# ExternalConnections.net
KiCad netlist of a schematic drawn in Altium Designer
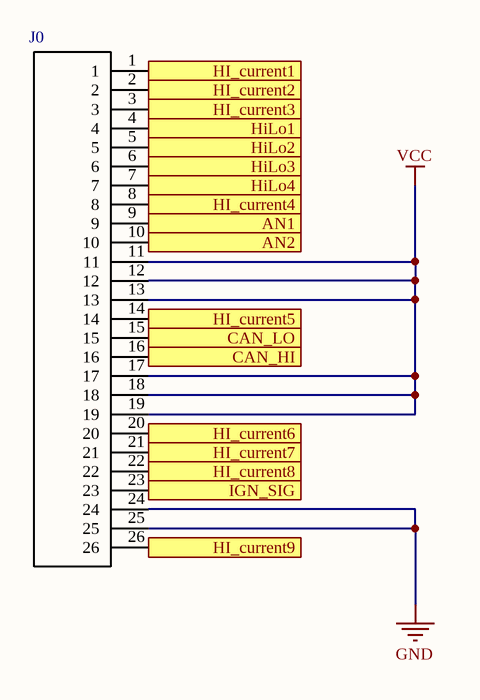
[diagram p0: ExternalConnections.SchDoc]

(export (version "E")
  (design (tool "Eeschema 10.0.6"))
  (components
    (comp (ref "J0")
      (value "6473418-1")
      (footprint "*TE_6473418-1")
      (description "Conn Shrouded Header PIN 26 POS 1.5mm Solder ST Thru-Hole Automotive Tube")
      (fields (field (name "DIGI-KEY_PART_NUMBER") "A121634-ND") (field (name "MF") "TE Connectivity"))
      (libsource (lib "6473418-1") (part "6473418-1"))
    )
  )
  (nets
    (net (code "1") (name "/AN1") (class "Default")
      (node (ref "J0") (pin "9") (pinfunction "9_9") (pintype "passive"))
    )
    (net (code "2") (name "/AN2") (class "Default")
      (node (ref "J0") (pin "10") (pinfunction "10_10") (pintype "passive"))
    )
    (net (code "3") (name "/CAN_HI") (class "Default")
      (node (ref "J0") (pin "16") (pinfunction "16_16") (pintype "passive"))
    )
    (net (code "4") (name "/CAN_LO") (class "Default")
      (node (ref "J0") (pin "15") (pinfunction "15_15") (pintype "passive"))
    )
    (net (code "5") (name "/HI_current1") (class "Default")
      (node (ref "J0") (pin "1") (pinfunction "1_1") (pintype "passive"))
    )
    (net (code "6") (name "/HI_current2") (class "Default")
      (node (ref "J0") (pin "2") (pinfunction "2_2") (pintype "passive"))
    )
    (net (code "7") (name "/HI_current3") (class "Default")
      (node (ref "J0") (pin "3") (pinfunction "3_3") (pintype "passive"))
    )
    (net (code "8") (name "/HI_current4") (class "Default")
      (node (ref "J0") (pin "8") (pinfunction "8_8") (pintype "passive"))
    )
    (net (code "9") (name "/HI_current5") (class "Default")
      (node (ref "J0") (pin "14") (pinfunction "14_14") (pintype "passive"))
    )
    (net (code "10") (name "/HI_current6") (class "Default")
      (node (ref "J0") (pin "20") (pinfunction "20_20") (pintype "passive"))
    )
    (net (code "11") (name "/HI_current7") (class "Default")
      (node (ref "J0") (pin "21") (pinfunction "21_21") (pintype "passive"))
    )
    (net (code "12") (name "/HI_current8") (class "Default")
      (node (ref "J0") (pin "22") (pinfunction "22_22") (pintype "passive"))
    )
    (net (code "13") (name "/HI_current9") (class "Default")
      (node (ref "J0") (pin "26") (pinfunction "26_26") (pintype "passive"))
    )
    (net (code "14") (name "/HiLo1") (class "Default")
      (node (ref "J0") (pin "4") (pinfunction "4_4") (pintype "passive"))
    )
    (net (code "15") (name "/HiLo2") (class "Default")
      (node (ref "J0") (pin "5") (pinfunction "5_5") (pintype "passive"))
    )
    (net (code "16") (name "/HiLo3") (class "Default")
      (node (ref "J0") (pin "6") (pinfunction "6_6") (pintype "passive"))
    )
    (net (code "17") (name "/HiLo4") (class "Default")
      (node (ref "J0") (pin "7") (pinfunction "7_7") (pintype "passive"))
    )
    (net (code "18") (name "/IGN_SIG") (class "Default")
      (node (ref "J0") (pin "23") (pinfunction "23_23") (pintype "passive"))
    )
    (net (code "19") (name "GND") (class "Default")
      (node (ref "J0") (pin "24") (pinfunction "24_24") (pintype "passive"))
      (node (ref "J0") (pin "25") (pinfunction "25_25") (pintype "passive"))
    )
    (net (code "20") (name "VCC") (class "Default")
      (node (ref "J0") (pin "11") (pinfunction "11_11") (pintype "passive"))
      (node (ref "J0") (pin "12") (pinfunction "12_12") (pintype "passive"))
      (node (ref "J0") (pin "13") (pinfunction "13_13") (pintype "passive"))
      (node (ref "J0") (pin "17") (pinfunction "17_17") (pintype "passive"))
      (node (ref "J0") (pin "18") (pinfunction "18_18") (pintype "passive"))
      (node (ref "J0") (pin "19") (pinfunction "19_19") (pintype "passive"))
    )
  )
)
